# polarshield3_0c-opl.net
KiCad netlist of a schematic drawn in EAGLE
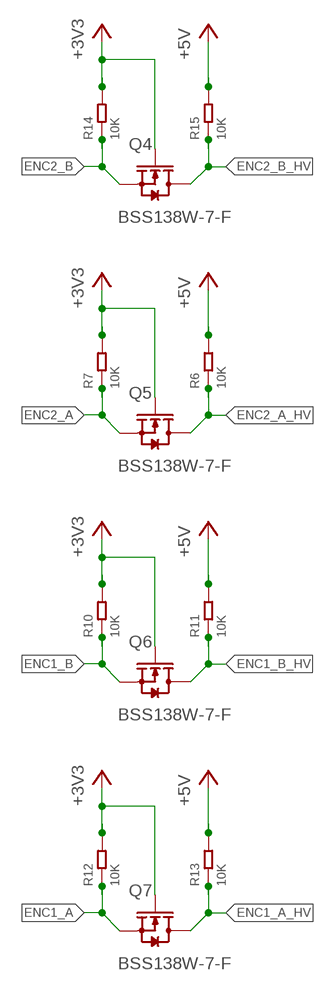
[diagram p0: schematic, sheet 1, part 1 of 2]
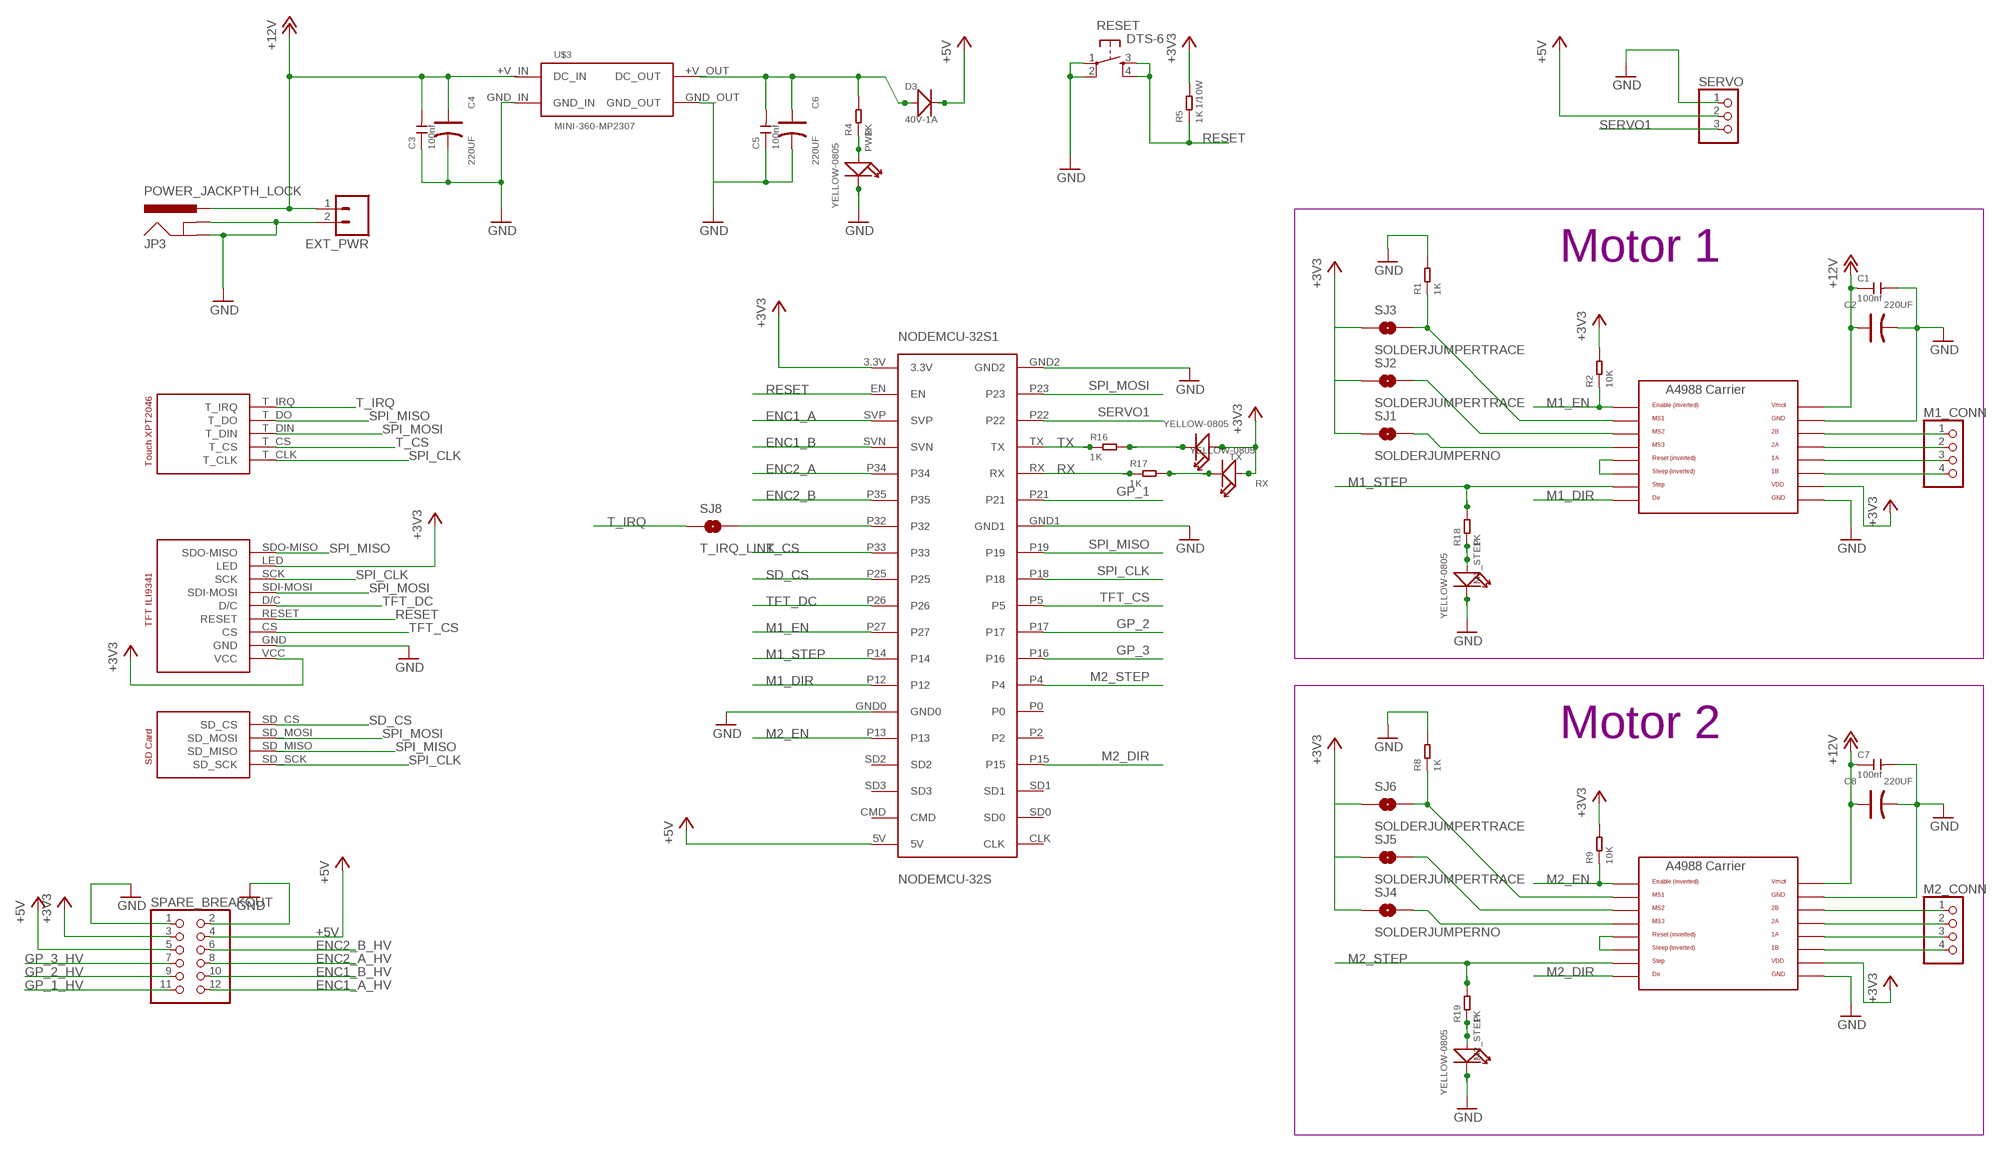
[diagram p1: schematic, sheet 1, part 2 of 2]

(export (version "E")
  (design (tool "Eeschema 10.0.6"))
  (components
    (comp (ref "C1")
      (value "100nf")
      (footprint "eagle-import:C0603")
      (fields (field (name "MPN") "CC0603KRX7R9BB104"))
      (libsource (lib "eagle-import") (part "CERAMIC-100NF-50V-10%-X7R(0603)"))
    )
    (comp (ref "C2")
      (value "220UF")
      (footprint "eagle-import:ELECTRO-SMD-C-6MM")
      (fields (field (name "MPN") "CS1E221M-CRE77"))
      (libsource (lib "eagle-import") (part "ALUMINUM-SMD-220UF-16V(D6.3-H7.7MM)"))
    )
    (comp (ref "C3")
      (value "100nf")
      (footprint "eagle-import:C0603")
      (fields (field (name "MPN") "CC0603KRX7R9BB104"))
      (libsource (lib "eagle-import") (part "CERAMIC-100NF-50V-10%-X7R(0603)"))
    )
    (comp (ref "C4")
      (value "220UF")
      (footprint "eagle-import:ELECTRO-SMD-C-6MM")
      (fields (field (name "MPN") "CS1E221M-CRE77"))
      (libsource (lib "eagle-import") (part "ALUMINUM-SMD-220UF-16V(D6.3-H7.7MM)"))
    )
    (comp (ref "C5")
      (value "100nf")
      (footprint "eagle-import:C0603")
      (fields (field (name "MPN") "CC0603KRX7R9BB104"))
      (libsource (lib "eagle-import") (part "CERAMIC-100NF-50V-10%-X7R(0603)"))
    )
    (comp (ref "C6")
      (value "220UF")
      (footprint "eagle-import:ELECTRO-SMD-C-6MM")
      (fields (field (name "MPN") "CS1E221M-CRE77"))
      (libsource (lib "eagle-import") (part "ALUMINUM-SMD-220UF-16V(D6.3-H7.7MM)"))
    )
    (comp (ref "C7")
      (value "100nf")
      (footprint "eagle-import:C0603")
      (fields (field (name "MPN") "CC0603KRX7R9BB104"))
      (libsource (lib "eagle-import") (part "CERAMIC-100NF-50V-10%-X7R(0603)"))
    )
    (comp (ref "C8")
      (value "220UF")
      (footprint "eagle-import:ELECTRO-SMD-C-6MM")
      (fields (field (name "MPN") "CS1E221M-CRE77"))
      (libsource (lib "eagle-import") (part "ALUMINUM-SMD-220UF-16V(D6.3-H7.7MM)"))
    )
    (comp (ref "D3")
      (value "40V-1A")
      (footprint "eagle-import:DO-214AC")
      (fields (field (name "MPN") "1N5819"))
      (libsource (lib "eagle-import") (part "SMD-DIODE-SCHOTTKY-40V-1A(DO-214AC)"))
    )
    (comp (ref "EXT_PWR")
      (value "M02PTH")
      (footprint "eagle-import:1X02")
      (libsource (lib "eagle-import") (part "M02PTH"))
    )
    (comp (ref "JP3")
      (value "POWER_JACKPTH_LOCK")
      (footprint "eagle-import:POWER_JACK_PTH_LOCK")
      (libsource (lib "eagle-import") (part "POWER_JACKPTH_LOCK"))
    )
    (comp (ref "M1_CONN")
      (value "PINHD-1X4/90")
      (footprint "eagle-import:1X04_90")
      (libsource (lib "eagle-import") (part "PINHD-1X4/90"))
    )
    (comp (ref "M1_STEP")
      (value "YELLOW-0805")
      (footprint "eagle-import:LED-0805")
      (fields (field (name "MPN") "17-215UYC/S530-A3/TR8"))
      (libsource (lib "eagle-import") (part "SMD-LED-CLEAR-YELLOW(0805)"))
    )
    (comp (ref "M2_CONN")
      (value "PINHD-1X4/90")
      (footprint "eagle-import:1X04_90")
      (libsource (lib "eagle-import") (part "PINHD-1X4/90"))
    )
    (comp (ref "M2_STEP")
      (value "YELLOW-0805")
      (footprint "eagle-import:LED-0805")
      (fields (field (name "MPN") "17-215UYC/S530-A3/TR8"))
      (libsource (lib "eagle-import") (part "SMD-LED-CLEAR-YELLOW(0805)"))
    )
    (comp (ref "MOTOR_1")
      (value "A4988BREAKOUT")
      (footprint "eagle-import:A4988BREAKOUT")
      (libsource (lib "eagle-import") (part "A4988BREAKOUT"))
    )
    (comp (ref "MOTOR_2")
      (value "A4988BREAKOUT")
      (footprint "eagle-import:A4988BREAKOUT")
      (libsource (lib "eagle-import") (part "A4988BREAKOUT"))
    )
    (comp (ref "NODEMCU-32S1")
      (value "NODEMCU-32S")
      (footprint "eagle-import:NODEMCU-32S")
      (libsource (lib "eagle-import") (part "NODEMCU-32S"))
    )
    (comp (ref "PWR")
      (value "YELLOW-0805")
      (footprint "eagle-import:LED-0805")
      (fields (field (name "MPN") "17-215UYC/S530-A3/TR8"))
      (libsource (lib "eagle-import") (part "SMD-LED-CLEAR-YELLOW(0805)"))
    )
    (comp (ref "Q4")
      (value "BSS138W-7-F")
      (footprint "eagle-import:SOT-23")
      (libsource (lib "eagle-import") (part "SMD-MOSFET-N-CH-50V-200MA-BSS138W-7-F(SOT-23)"))
    )
    (comp (ref "Q5")
      (value "BSS138W-7-F")
      (footprint "eagle-import:SOT-23")
      (libsource (lib "eagle-import") (part "SMD-MOSFET-N-CH-50V-200MA-BSS138W-7-F(SOT-23)"))
    )
    (comp (ref "Q6")
      (value "BSS138W-7-F")
      (footprint "eagle-import:SOT-23")
      (libsource (lib "eagle-import") (part "SMD-MOSFET-N-CH-50V-200MA-BSS138W-7-F(SOT-23)"))
    )
    (comp (ref "Q7")
      (value "BSS138W-7-F")
      (footprint "eagle-import:SOT-23")
      (libsource (lib "eagle-import") (part "SMD-MOSFET-N-CH-50V-200MA-BSS138W-7-F(SOT-23)"))
    )
    (comp (ref "R1")
      (value "1K")
      (footprint "eagle-import:R0603")
      (fields (field (name "MPN") "RC0603JR-071KL"))
      (libsource (lib "eagle-import") (part "SMD-RES-1K-5%-1/10W(0603)"))
    )
    (comp (ref "R2")
      (value "10K")
      (footprint "eagle-import:R0603")
      (fields (field (name "MPN") "RC0603JR-0710KL"))
      (libsource (lib "eagle-import") (part "SMD-RES-10K-5%-1/10W(0603)"))
    )
    (comp (ref "R4")
      (value "1K")
      (footprint "eagle-import:R0603")
      (fields (field (name "MPN") "RC0603JR-071KL"))
      (libsource (lib "eagle-import") (part "SMD-RES-1K-5%-1/10W(0603)"))
    )
    (comp (ref "R5")
      (value "1K 1/10W")
      (footprint "eagle-import:R0603")
      (fields (field (name "MPN") "RC0603JR-071KL"))
      (libsource (lib "eagle-import") (part "SMD-RES-1K-5%-1/10W(0603)"))
    )
    (comp (ref "R6")
      (value "10K")
      (footprint "eagle-import:R0603")
      (fields (field (name "MPN") "RC0603JR-0710KL"))
      (libsource (lib "eagle-import") (part "SMD-RES-10K-5%-1/10W(0603)"))
    )
    (comp (ref "R7")
      (value "10K")
      (footprint "eagle-import:R0603")
      (fields (field (name "MPN") "RC0603JR-0710KL"))
      (libsource (lib "eagle-import") (part "SMD-RES-10K-5%-1/10W(0603)"))
    )
    (comp (ref "R8")
      (value "1K")
      (footprint "eagle-import:R0603")
      (fields (field (name "MPN") "RC0603JR-071KL"))
      (libsource (lib "eagle-import") (part "SMD-RES-1K-5%-1/10W(0603)"))
    )
    (comp (ref "R9")
      (value "10K")
      (footprint "eagle-import:R0603")
      (fields (field (name "MPN") "RC0603JR-0710KL"))
      (libsource (lib "eagle-import") (part "SMD-RES-10K-5%-1/10W(0603)"))
    )
    (comp (ref "R10")
      (value "10K")
      (footprint "eagle-import:R0603")
      (fields (field (name "MPN") "RC0603JR-0710KL"))
      (libsource (lib "eagle-import") (part "SMD-RES-10K-5%-1/10W(0603)"))
    )
    (comp (ref "R11")
      (value "10K")
      (footprint "eagle-import:R0603")
      (fields (field (name "MPN") "RC0603JR-0710KL"))
      (libsource (lib "eagle-import") (part "SMD-RES-10K-5%-1/10W(0603)"))
    )
    (comp (ref "R12")
      (value "10K")
      (footprint "eagle-import:R0603")
      (fields (field (name "MPN") "RC0603JR-0710KL"))
      (libsource (lib "eagle-import") (part "SMD-RES-10K-5%-1/10W(0603)"))
    )
    (comp (ref "R13")
      (value "10K")
      (footprint "eagle-import:R0603")
      (fields (field (name "MPN") "RC0603JR-0710KL"))
      (libsource (lib "eagle-import") (part "SMD-RES-10K-5%-1/10W(0603)"))
    )
    (comp (ref "R14")
      (value "10K")
      (footprint "eagle-import:R0603")
      (fields (field (name "MPN") "RC0603JR-0710KL"))
      (libsource (lib "eagle-import") (part "SMD-RES-10K-5%-1/10W(0603)"))
    )
    (comp (ref "R15")
      (value "10K")
      (footprint "eagle-import:R0603")
      (fields (field (name "MPN") "RC0603JR-0710KL"))
      (libsource (lib "eagle-import") (part "SMD-RES-10K-5%-1/10W(0603)"))
    )
    (comp (ref "R16")
      (value "1K")
      (footprint "eagle-import:R0603")
      (fields (field (name "MPN") "RC0603JR-071KL"))
      (libsource (lib "eagle-import") (part "SMD-RES-1K-5%-1/10W(0603)"))
    )
    (comp (ref "R17")
      (value "1K")
      (footprint "eagle-import:R0603")
      (fields (field (name "MPN") "RC0603JR-071KL"))
      (libsource (lib "eagle-import") (part "SMD-RES-1K-5%-1/10W(0603)"))
    )
    (comp (ref "R18")
      (value "1K")
      (footprint "eagle-import:R0603")
      (fields (field (name "MPN") "RC0603JR-071KL"))
      (libsource (lib "eagle-import") (part "SMD-RES-1K-5%-1/10W(0603)"))
    )
    (comp (ref "R19")
      (value "1K")
      (footprint "eagle-import:R0603")
      (fields (field (name "MPN") "RC0603JR-071KL"))
      (libsource (lib "eagle-import") (part "SMD-RES-1K-5%-1/10W(0603)"))
    )
    (comp (ref "RESET")
      (value "DTS-6")
      (footprint "eagle-import:DTS-6")
      (libsource (lib "eagle-import") (part "DTS-6"))
    )
    (comp (ref "RX")
      (value "YELLOW-0805")
      (footprint "eagle-import:LED-0805")
      (fields (field (name "MPN") "17-215UYC/S530-A3/TR8"))
      (libsource (lib "eagle-import") (part "SMD-LED-CLEAR-YELLOW(0805)"))
    )
    (comp (ref "SERVO")
      (value "PINHD-1X3/90")
      (footprint "eagle-import:1X03_90")
      (libsource (lib "eagle-import") (part "PINHD-1X3/90"))
    )
    (comp (ref "SJ1")
      (value "SOLDERJUMPERNO")
      (footprint "eagle-import:SJ_2S-NO")
      (libsource (lib "eagle-import") (part "polargraph3_SOLDERJUMPERNO"))
    )
    (comp (ref "SJ2")
      (value "SOLDERJUMPERTRACE")
      (footprint "eagle-import:SJ_2S-TRACE")
      (libsource (lib "eagle-import") (part "polargraph3_SOLDERJUMPERTRACE"))
    )
    (comp (ref "SJ3")
      (value "SOLDERJUMPERTRACE")
      (footprint "eagle-import:SJ_2S-TRACE")
      (libsource (lib "eagle-import") (part "polargraph3_SOLDERJUMPERTRACE"))
    )
    (comp (ref "SJ4")
      (value "SOLDERJUMPERNO")
      (footprint "eagle-import:SJ_2S-NO")
      (libsource (lib "eagle-import") (part "polargraph3_SOLDERJUMPERNO"))
    )
    (comp (ref "SJ5")
      (value "SOLDERJUMPERTRACE")
      (footprint "eagle-import:SJ_2S-TRACE")
      (libsource (lib "eagle-import") (part "polargraph3_SOLDERJUMPERTRACE"))
    )
    (comp (ref "SJ6")
      (value "SOLDERJUMPERTRACE")
      (footprint "eagle-import:SJ_2S-TRACE")
      (libsource (lib "eagle-import") (part "polargraph3_SOLDERJUMPERTRACE"))
    )
    (comp (ref "SJ8")
      (value "T_IRQ_LINK")
      (footprint "eagle-import:SJ_2S-NO")
      (libsource (lib "eagle-import") (part "SOLDERJUMPERNO"))
    )
    (comp (ref "SPARE_BREAKOUT")
      (value "PINHD-2X6")
      (footprint "eagle-import:2X06")
      (libsource (lib "eagle-import") (part "PINHD-2X6"))
    )
    (comp (ref "TX")
      (value "YELLOW-0805")
      (footprint "eagle-import:LED-0805")
      (fields (field (name "MPN") "17-215UYC/S530-A3/TR8"))
      (libsource (lib "eagle-import") (part "SMD-LED-CLEAR-YELLOW(0805)"))
    )
    (comp (ref "U$2")
      (value "2.4_TFT_SPI_TOUCH_SD")
      (footprint "eagle-import:2.4_TFT_SPI_TOUCH_SD")
      (libsource (lib "eagle-import") (part "2.4_TFT_SPI_TOUCH_SD"))
    )
    (comp (ref "U$3")
      (value "MINI-360-MP2307")
      (footprint "eagle-import:MINI-360-MP2307")
      (libsource (lib "eagle-import") (part "MINI-360-MP2307"))
    )
  )
  (nets
    (net (code "1") (name "+3V3") (class "Default")
      (node (ref "MOTOR_1") (pin "VDD") (pinfunction "VDD_VDD") (pintype "power_in"))
      (node (ref "MOTOR_2") (pin "VDD") (pinfunction "VDD_VDD") (pintype "power_in"))
      (node (ref "NODEMCU-32S1") (pin "3.3V") (pinfunction "3.3V_3.3V") (pintype "bidirectional"))
      (node (ref "Q4") (pin "1") (pinfunction "G_1") (pintype "passive"))
      (node (ref "Q5") (pin "1") (pinfunction "G_1") (pintype "passive"))
      (node (ref "Q6") (pin "1") (pinfunction "G_1") (pintype "passive"))
      (node (ref "Q7") (pin "1") (pinfunction "G_1") (pintype "passive"))
      (node (ref "R10") (pin "2") (pinfunction "2_2") (pintype "passive"))
      (node (ref "R12") (pin "2") (pinfunction "2_2") (pintype "passive"))
      (node (ref "R14") (pin "2") (pinfunction "2_2") (pintype "passive"))
      (node (ref "R2") (pin "2") (pinfunction "2_2") (pintype "passive"))
      (node (ref "R5") (pin "2") (pinfunction "2_2") (pintype "passive"))
      (node (ref "R7") (pin "2") (pinfunction "2_2") (pintype "passive"))
      (node (ref "R9") (pin "2") (pinfunction "2_2") (pintype "passive"))
      (node (ref "RX") (pin "+") (pinfunction "+_+") (pintype "passive"))
      (node (ref "SJ1") (pin "1") (pinfunction "1_1") (pintype "passive"))
      (node (ref "SJ2") (pin "1") (pinfunction "1_1") (pintype "passive"))
      (node (ref "SJ3") (pin "1") (pinfunction "1_1") (pintype "passive"))
      (node (ref "SJ4") (pin "1") (pinfunction "1_1") (pintype "passive"))
      (node (ref "SJ5") (pin "1") (pinfunction "1_1") (pintype "passive"))
      (node (ref "SJ6") (pin "1") (pinfunction "1_1") (pintype "passive"))
      (node (ref "SPARE_BREAKOUT") (pin "3") (pinfunction "3_3") (pintype "passive"))
      (node (ref "TX") (pin "+") (pinfunction "+_+") (pintype "passive"))
      (node (ref "U$2") (pin "LED") (pinfunction "LED_LED") (pintype "bidirectional"))
      (node (ref "U$2") (pin "VCC") (pinfunction "VCC_VCC") (pintype "bidirectional"))
    )
    (net (code "2") (name "+5V") (class "Default")
      (node (ref "D3") (pin "2") (pinfunction "-_2") (pintype "passive"))
      (node (ref "NODEMCU-32S1") (pin "5V") (pinfunction "5V_5V") (pintype "bidirectional"))
      (node (ref "R11") (pin "2") (pinfunction "2_2") (pintype "passive"))
      (node (ref "R13") (pin "2") (pinfunction "2_2") (pintype "passive"))
      (node (ref "R15") (pin "2") (pinfunction "2_2") (pintype "passive"))
      (node (ref "R6") (pin "2") (pinfunction "2_2") (pintype "passive"))
      (node (ref "SERVO") (pin "2") (pinfunction "2_2") (pintype "passive"))
      (node (ref "SPARE_BREAKOUT") (pin "4") (pinfunction "4_4") (pintype "passive"))
      (node (ref "SPARE_BREAKOUT") (pin "5") (pinfunction "5_5") (pintype "passive"))
    )
    (net (code "3") (name "+12V") (class "Default")
      (node (ref "C1") (pin "1") (pinfunction "1_1") (pintype "passive"))
      (node (ref "C2") (pin "+") (pinfunction "+_+") (pintype "passive"))
      (node (ref "C3") (pin "2") (pinfunction "2_2") (pintype "passive"))
      (node (ref "C4") (pin "+") (pinfunction "+_+") (pintype "passive"))
      (node (ref "C7") (pin "1") (pinfunction "1_1") (pintype "passive"))
      (node (ref "C8") (pin "+") (pinfunction "+_+") (pintype "passive"))
      (node (ref "EXT_PWR") (pin "1") (pinfunction "1_1") (pintype "passive"))
      (node (ref "JP3") (pin "PWR") (pinfunction "PWR_PWR") (pintype "bidirectional"))
      (node (ref "MOTOR_1") (pin "VMOT") (pinfunction "VMOT_VMOT") (pintype "power_in"))
      (node (ref "MOTOR_2") (pin "VMOT") (pinfunction "VMOT_VMOT") (pintype "power_in"))
      (node (ref "U$3") (pin "+V_IN") (pinfunction "DC_IN_+V_IN") (pintype "bidirectional"))
    )
    (net (code "4") (name "/GP_1") (class "Default")
      (node (ref "NODEMCU-32S1") (pin "P21") (pinfunction "P21_P21") (pintype "bidirectional"))
    )
    (net (code "5") (name "/GP_1_HV") (class "Default")
      (node (ref "SPARE_BREAKOUT") (pin "11") (pinfunction "11_11") (pintype "passive"))
    )
    (net (code "6") (name "/GP_2") (class "Default")
      (node (ref "NODEMCU-32S1") (pin "P17") (pinfunction "P17_P17") (pintype "bidirectional"))
    )
    (net (code "7") (name "/GP_2_HV") (class "Default")
      (node (ref "SPARE_BREAKOUT") (pin "9") (pinfunction "9_9") (pintype "passive"))
    )
    (net (code "8") (name "/GP_3") (class "Default")
      (node (ref "NODEMCU-32S1") (pin "P16") (pinfunction "P16_P16") (pintype "bidirectional"))
    )
    (net (code "9") (name "/GP_3_HV") (class "Default")
      (node (ref "SPARE_BREAKOUT") (pin "7") (pinfunction "7_7") (pintype "passive"))
    )
    (net (code "10") (name "/M1_DIR") (class "Default")
      (node (ref "MOTOR_1") (pin "DIR") (pinfunction "DIR_DIR") (pintype "input"))
      (node (ref "NODEMCU-32S1") (pin "P12") (pinfunction "P12_P12") (pintype "bidirectional"))
    )
    (net (code "11") (name "/M1_EN") (class "Default")
      (node (ref "MOTOR_1") (pin "EN") (pinfunction "EN_EN") (pintype "input"))
      (node (ref "NODEMCU-32S1") (pin "P27") (pinfunction "P27_P27") (pintype "bidirectional"))
      (node (ref "R2") (pin "1") (pinfunction "1_1") (pintype "passive"))
    )
    (net (code "12") (name "/M1_STEP") (class "Default")
      (node (ref "MOTOR_1") (pin "STEP") (pinfunction "STEP_STEP") (pintype "input"))
      (node (ref "NODEMCU-32S1") (pin "P14") (pinfunction "P14_P14") (pintype "bidirectional"))
      (node (ref "R18") (pin "2") (pinfunction "2_2") (pintype "passive"))
    )
    (net (code "13") (name "/M2_DIR") (class "Default")
      (node (ref "MOTOR_2") (pin "DIR") (pinfunction "DIR_DIR") (pintype "input"))
      (node (ref "NODEMCU-32S1") (pin "P15") (pinfunction "P15_P15") (pintype "bidirectional"))
    )
    (net (code "14") (name "/M2_EN") (class "Default")
      (node (ref "MOTOR_2") (pin "EN") (pinfunction "EN_EN") (pintype "input"))
      (node (ref "NODEMCU-32S1") (pin "P13") (pinfunction "P13_P13") (pintype "bidirectional"))
      (node (ref "R9") (pin "1") (pinfunction "1_1") (pintype "passive"))
    )
    (net (code "15") (name "/M2_STEP") (class "Default")
      (node (ref "MOTOR_2") (pin "STEP") (pinfunction "STEP_STEP") (pintype "input"))
      (node (ref "NODEMCU-32S1") (pin "P4") (pinfunction "P4_P4") (pintype "bidirectional"))
      (node (ref "R19") (pin "2") (pinfunction "2_2") (pintype "passive"))
    )
    (net (code "16") (name "/RESET") (class "Default")
      (node (ref "NODEMCU-32S1") (pin "EN") (pinfunction "EN_EN") (pintype "bidirectional"))
      (node (ref "R5") (pin "1") (pinfunction "1_1") (pintype "passive"))
      (node (ref "RESET") (pin "3") (pinfunction "3_3") (pintype "passive"))
      (node (ref "RESET") (pin "4") (pinfunction "4_4") (pintype "passive"))
      (node (ref "U$2") (pin "RESET") (pinfunction "RESET_RESET") (pintype "bidirectional"))
    )
    (net (code "17") (name "/RX") (class "Default")
      (node (ref "NODEMCU-32S1") (pin "RX") (pinfunction "RX_RX") (pintype "bidirectional"))
      (node (ref "R17") (pin "1") (pinfunction "1_1") (pintype "passive"))
    )
    (net (code "18") (name "/SD_CS") (class "Default")
      (node (ref "NODEMCU-32S1") (pin "P25") (pinfunction "P25_P25") (pintype "bidirectional"))
      (node (ref "U$2") (pin "SD_CS") (pinfunction "SD_CS_SD_CS") (pintype "bidirectional"))
    )
    (net (code "19") (name "/SERVO1") (class "Default")
      (node (ref "NODEMCU-32S1") (pin "P22") (pinfunction "P22_P22") (pintype "bidirectional"))
      (node (ref "SERVO") (pin "3") (pinfunction "3_3") (pintype "passive"))
    )
    (net (code "20") (name "/SPI_CLK") (class "Default")
      (node (ref "NODEMCU-32S1") (pin "P18") (pinfunction "P18_P18") (pintype "bidirectional"))
      (node (ref "U$2") (pin "SCK") (pinfunction "SCK_SCK") (pintype "bidirectional"))
      (node (ref "U$2") (pin "SD_SCK") (pinfunction "SD_SCK_SD_SCK") (pintype "bidirectional"))
      (node (ref "U$2") (pin "T_CLK") (pinfunction "T_CLK_T_CLK") (pintype "input"))
    )
    (net (code "21") (name "/SPI_MISO") (class "Default")
      (node (ref "NODEMCU-32S1") (pin "P19") (pinfunction "P19_P19") (pintype "bidirectional"))
      (node (ref "U$2") (pin "SDO-MISO") (pinfunction "SDO-MISO_SDO-MISO") (pintype "bidirectional"))
      (node (ref "U$2") (pin "SD_MISO") (pinfunction "SD_MISO_SD_MISO") (pintype "bidirectional"))
      (node (ref "U$2") (pin "T_DO") (pinfunction "T_DO_T_DO") (pintype "output"))
    )
    (net (code "22") (name "/SPI_MOSI") (class "Default")
      (node (ref "NODEMCU-32S1") (pin "P23") (pinfunction "P23_P23") (pintype "bidirectional"))
      (node (ref "U$2") (pin "SDI-MOSI") (pinfunction "SDI-MOSI_SDI-MOSI") (pintype "bidirectional"))
      (node (ref "U$2") (pin "SD_MOSI") (pinfunction "SD_MOSI_SD_MOSI") (pintype "bidirectional"))
      (node (ref "U$2") (pin "T_DIN") (pinfunction "T_DIN_T_DIN") (pintype "input"))
    )
    (net (code "23") (name "/TFT_CS") (class "Default")
      (node (ref "NODEMCU-32S1") (pin "P5") (pinfunction "P5_P5") (pintype "bidirectional"))
      (node (ref "U$2") (pin "CS") (pinfunction "CS_CS") (pintype "bidirectional"))
    )
    (net (code "24") (name "/TFT_DC") (class "Default")
      (node (ref "NODEMCU-32S1") (pin "P26") (pinfunction "P26_P26") (pintype "bidirectional"))
      (node (ref "U$2") (pin "D/C") (pinfunction "D/C_D/C") (pintype "bidirectional"))
    )
    (net (code "25") (name "/TX") (class "Default")
      (node (ref "NODEMCU-32S1") (pin "TX") (pinfunction "TX_TX") (pintype "bidirectional"))
      (node (ref "R16") (pin "1") (pinfunction "1_1") (pintype "passive"))
    )
    (net (code "26") (name "/T_CS") (class "Default")
      (node (ref "NODEMCU-32S1") (pin "P33") (pinfunction "P33_P33") (pintype "bidirectional"))
      (node (ref "U$2") (pin "T_CS") (pinfunction "T_CS_T_CS") (pintype "output"))
    )
    (net (code "27") (name "/T_IRQ") (class "Default")
      (node (ref "SJ8") (pin "1") (pinfunction "1_1") (pintype "passive"))
      (node (ref "U$2") (pin "T_IRQ") (pinfunction "T_IRQ_T_IRQ") (pintype "output"))
    )
    (net (code "28") (name "ENC1_A") (class "Default")
      (node (ref "NODEMCU-32S1") (pin "SVP") (pinfunction "SVP_SVP") (pintype "bidirectional"))
      (node (ref "Q7") (pin "2") (pinfunction "S_2") (pintype "passive"))
      (node (ref "R12") (pin "1") (pinfunction "1_1") (pintype "passive"))
    )
    (net (code "29") (name "ENC1_A_HV") (class "Default")
      (node (ref "Q7") (pin "3") (pinfunction "D_3") (pintype "passive"))
      (node (ref "R13") (pin "1") (pinfunction "1_1") (pintype "passive"))
      (node (ref "SPARE_BREAKOUT") (pin "12") (pinfunction "12_12") (pintype "passive"))
    )
    (net (code "30") (name "ENC1_B") (class "Default")
      (node (ref "NODEMCU-32S1") (pin "SVN") (pinfunction "SVN_SVN") (pintype "bidirectional"))
      (node (ref "Q6") (pin "2") (pinfunction "S_2") (pintype "passive"))
      (node (ref "R10") (pin "1") (pinfunction "1_1") (pintype "passive"))
    )
    (net (code "31") (name "ENC1_B_HV") (class "Default")
      (node (ref "Q6") (pin "3") (pinfunction "D_3") (pintype "passive"))
      (node (ref "R11") (pin "1") (pinfunction "1_1") (pintype "passive"))
      (node (ref "SPARE_BREAKOUT") (pin "10") (pinfunction "10_10") (pintype "passive"))
    )
    (net (code "32") (name "ENC2_A") (class "Default")
      (node (ref "NODEMCU-32S1") (pin "P34") (pinfunction "P34_P34") (pintype "bidirectional"))
      (node (ref "Q5") (pin "2") (pinfunction "S_2") (pintype "passive"))
      (node (ref "R7") (pin "1") (pinfunction "1_1") (pintype "passive"))
    )
    (net (code "33") (name "ENC2_A_HV") (class "Default")
      (node (ref "Q5") (pin "3") (pinfunction "D_3") (pintype "passive"))
      (node (ref "R6") (pin "1") (pinfunction "1_1") (pintype "passive"))
      (node (ref "SPARE_BREAKOUT") (pin "8") (pinfunction "8_8") (pintype "passive"))
    )
    (net (code "34") (name "ENC2_B") (class "Default")
      (node (ref "NODEMCU-32S1") (pin "P35") (pinfunction "P35_P35") (pintype "bidirectional"))
      (node (ref "Q4") (pin "2") (pinfunction "S_2") (pintype "passive"))
      (node (ref "R14") (pin "1") (pinfunction "1_1") (pintype "passive"))
    )
    (net (code "35") (name "ENC2_B_HV") (class "Default")
      (node (ref "Q4") (pin "3") (pinfunction "D_3") (pintype "passive"))
      (node (ref "R15") (pin "1") (pinfunction "1_1") (pintype "passive"))
      (node (ref "SPARE_BREAKOUT") (pin "6") (pinfunction "6_6") (pintype "passive"))
    )
    (net (code "36") (name "GND") (class "Default")
      (node (ref "C1") (pin "2") (pinfunction "2_2") (pintype "passive"))
      (node (ref "C2") (pin "-") (pinfunction "-_-") (pintype "passive"))
      (node (ref "C3") (pin "1") (pinfunction "1_1") (pintype "passive"))
      (node (ref "C4") (pin "-") (pinfunction "-_-") (pintype "passive"))
      (node (ref "C5") (pin "1") (pinfunction "1_1") (pintype "passive"))
      (node (ref "C6") (pin "-") (pinfunction "-_-") (pintype "passive"))
      (node (ref "C7") (pin "2") (pinfunction "2_2") (pintype "passive"))
      (node (ref "C8") (pin "-") (pinfunction "-_-") (pintype "passive"))
      (node (ref "EXT_PWR") (pin "2") (pinfunction "2_2") (pintype "passive"))
      (node (ref "JP3") (pin "GND") (pinfunction "GND_GND") (pintype "bidirectional"))
      (node (ref "JP3") (pin "GNDBREAK") (pinfunction "GNDBREAK_GNDBREAK") (pintype "bidirectional"))
      (node (ref "M1_STEP") (pin "-") (pinfunction "-_-") (pintype "passive"))
      (node (ref "M2_STEP") (pin "-") (pinfunction "-_-") (pintype "passive"))
      (node (ref "MOTOR_1") (pin "GND") (pinfunction "GND_GND") (pintype "power_in"))
      (node (ref "MOTOR_1") (pin "GND@0") (pinfunction "GND_GND@0") (pintype "power_in"))
      (node (ref "MOTOR_2") (pin "GND") (pinfunction "GND_GND") (pintype "power_in"))
      (node (ref "MOTOR_2") (pin "GND@0") (pinfunction "GND_GND@0") (pintype "power_in"))
      (node (ref "NODEMCU-32S1") (pin "GND0") (pinfunction "GND0_GND0") (pintype "bidirectional"))
      (node (ref "NODEMCU-32S1") (pin "GND1") (pinfunction "GND1_GND1") (pintype "bidirectional"))
      (node (ref "NODEMCU-32S1") (pin "GND2") (pinfunction "GND2_GND2") (pintype "bidirectional"))
      (node (ref "PWR") (pin "-") (pinfunction "-_-") (pintype "passive"))
      (node (ref "R1") (pin "2") (pinfunction "2_2") (pintype "passive"))
      (node (ref "R8") (pin "2") (pinfunction "2_2") (pintype "passive"))
      (node (ref "RESET") (pin "1") (pinfunction "1_1") (pintype "passive"))
      (node (ref "RESET") (pin "2") (pinfunction "2_2") (pintype "passive"))
      (node (ref "SERVO") (pin "1") (pinfunction "1_1") (pintype "passive"))
      (node (ref "SPARE_BREAKOUT") (pin "1") (pinfunction "1_1") (pintype "passive"))
      (node (ref "SPARE_BREAKOUT") (pin "2") (pinfunction "2_2") (pintype "passive"))
      (node (ref "U$2") (pin "GND") (pinfunction "GND_GND") (pintype "bidirectional"))
      (node (ref "U$3") (pin "GND_IN") (pinfunction "GND_IN_GND_IN") (pintype "bidirectional"))
      (node (ref "U$3") (pin "GND_OUT") (pinfunction "GND_OUT_GND_OUT") (pintype "bidirectional"))
    )
    (net (code "37") (name "Net-(D3-+)") (class "Default")
      (node (ref "C5") (pin "2") (pinfunction "2_2") (pintype "passive"))
      (node (ref "C6") (pin "+") (pinfunction "+_+") (pintype "passive"))
      (node (ref "D3") (pin "1") (pinfunction "+_1") (pintype "passive"))
      (node (ref "R4") (pin "2") (pinfunction "2_2") (pintype "passive"))
      (node (ref "U$3") (pin "+V_OUT") (pinfunction "DC_OUT_+V_OUT") (pintype "bidirectional"))
    )
    (net (code "38") (name "Net-(M1_CONN-Pad1)") (class "Default")
      (node (ref "M1_CONN") (pin "1") (pinfunction "1_1") (pintype "passive"))
      (node (ref "MOTOR_1") (pin "2B") (pinfunction "2B_2B") (pintype "output"))
    )
    (net (code "39") (name "Net-(M1_CONN-Pad2)") (class "Default")
      (node (ref "M1_CONN") (pin "2") (pinfunction "2_2") (pintype "passive"))
      (node (ref "MOTOR_1") (pin "2A") (pinfunction "2A_2A") (pintype "output"))
    )
    (net (code "40") (name "Net-(M1_CONN-Pad3)") (class "Default")
      (node (ref "M1_CONN") (pin "3") (pinfunction "3_3") (pintype "passive"))
      (node (ref "MOTOR_1") (pin "1A") (pinfunction "1A_1A") (pintype "output"))
    )
    (net (code "41") (name "Net-(M1_CONN-Pad4)") (class "Default")
      (node (ref "M1_CONN") (pin "4") (pinfunction "4_4") (pintype "passive"))
      (node (ref "MOTOR_1") (pin "1B") (pinfunction "1B_1B") (pintype "output"))
    )
    (net (code "42") (name "Net-(M1_STEP-Pad+)") (class "Default")
      (node (ref "M1_STEP") (pin "+") (pinfunction "+_+") (pintype "passive"))
      (node (ref "R18") (pin "1") (pinfunction "1_1") (pintype "passive"))
    )
    (net (code "43") (name "Net-(M2_CONN-Pad1)") (class "Default")
      (node (ref "M2_CONN") (pin "1") (pinfunction "1_1") (pintype "passive"))
      (node (ref "MOTOR_2") (pin "2B") (pinfunction "2B_2B") (pintype "output"))
    )
    (net (code "44") (name "Net-(M2_CONN-Pad2)") (class "Default")
      (node (ref "M2_CONN") (pin "2") (pinfunction "2_2") (pintype "passive"))
      (node (ref "MOTOR_2") (pin "2A") (pinfunction "2A_2A") (pintype "output"))
    )
    (net (code "45") (name "Net-(M2_CONN-Pad3)") (class "Default")
      (node (ref "M2_CONN") (pin "3") (pinfunction "3_3") (pintype "passive"))
      (node (ref "MOTOR_2") (pin "1A") (pinfunction "1A_1A") (pintype "output"))
    )
    (net (code "46") (name "Net-(M2_CONN-Pad4)") (class "Default")
      (node (ref "M2_CONN") (pin "4") (pinfunction "4_4") (pintype "passive"))
      (node (ref "MOTOR_2") (pin "1B") (pinfunction "1B_1B") (pintype "output"))
    )
    (net (code "47") (name "Net-(M2_STEP-Pad+)") (class "Default")
      (node (ref "M2_STEP") (pin "+") (pinfunction "+_+") (pintype "passive"))
      (node (ref "R19") (pin "1") (pinfunction "1_1") (pintype "passive"))
    )
    (net (code "48") (name "Net-(MOTOR_1-PadMS1)") (class "Default")
      (node (ref "MOTOR_1") (pin "MS1") (pinfunction "MS1_MS1") (pintype "input"))
      (node (ref "R1") (pin "1") (pinfunction "1_1") (pintype "passive"))
      (node (ref "SJ3") (pin "2") (pinfunction "2_2") (pintype "passive"))
    )
    (net (code "49") (name "Net-(MOTOR_1-PadMS2)") (class "Default")
      (node (ref "MOTOR_1") (pin "MS2") (pinfunction "MS2_MS2") (pintype "input"))
      (node (ref "SJ2") (pin "2") (pinfunction "2_2") (pintype "passive"))
    )
    (net (code "50") (name "Net-(MOTOR_1-PadMS3)") (class "Default")
      (node (ref "MOTOR_1") (pin "MS3") (pinfunction "MS3_MS3") (pintype "input"))
      (node (ref "SJ1") (pin "2") (pinfunction "2_2") (pintype "passive"))
    )
    (net (code "51") (name "Net-(MOTOR_1-SLEEP)") (class "Default")
      (node (ref "MOTOR_1") (pin "RST") (pinfunction "RST_RST") (pintype "input"))
      (node (ref "MOTOR_1") (pin "SLP") (pinfunction "SLEEP_SLP") (pintype "input"))
    )
    (net (code "52") (name "Net-(MOTOR_2-PadMS1)") (class "Default")
      (node (ref "MOTOR_2") (pin "MS1") (pinfunction "MS1_MS1") (pintype "input"))
      (node (ref "R8") (pin "1") (pinfunction "1_1") (pintype "passive"))
      (node (ref "SJ6") (pin "2") (pinfunction "2_2") (pintype "passive"))
    )
    (net (code "53") (name "Net-(MOTOR_2-PadMS2)") (class "Default")
      (node (ref "MOTOR_2") (pin "MS2") (pinfunction "MS2_MS2") (pintype "input"))
      (node (ref "SJ5") (pin "2") (pinfunction "2_2") (pintype "passive"))
    )
    (net (code "54") (name "Net-(MOTOR_2-PadMS3)") (class "Default")
      (node (ref "MOTOR_2") (pin "MS3") (pinfunction "MS3_MS3") (pintype "input"))
      (node (ref "SJ4") (pin "2") (pinfunction "2_2") (pintype "passive"))
    )
    (net (code "55") (name "Net-(MOTOR_2-SLEEP)") (class "Default")
      (node (ref "MOTOR_2") (pin "RST") (pinfunction "RST_RST") (pintype "input"))
      (node (ref "MOTOR_2") (pin "SLP") (pinfunction "SLEEP_SLP") (pintype "input"))
    )
    (net (code "56") (name "Net-(NODEMCU-32S1-PadP32)") (class "Default")
      (node (ref "NODEMCU-32S1") (pin "P32") (pinfunction "P32_P32") (pintype "bidirectional"))
      (node (ref "SJ8") (pin "2") (pinfunction "2_2") (pintype "passive"))
    )
    (net (code "57") (name "Net-(PWR-Pad+)") (class "Default")
      (node (ref "PWR") (pin "+") (pinfunction "+_+") (pintype "passive"))
      (node (ref "R4") (pin "1") (pinfunction "1_1") (pintype "passive"))
    )
    (net (code "58") (name "Net-(R16-Pad2)") (class "Default")
      (node (ref "R16") (pin "2") (pinfunction "2_2") (pintype "passive"))
      (node (ref "TX") (pin "-") (pinfunction "-_-") (pintype "passive"))
    )
    (net (code "59") (name "Net-(R17-Pad2)") (class "Default")
      (node (ref "R17") (pin "2") (pinfunction "2_2") (pintype "passive"))
      (node (ref "RX") (pin "-") (pinfunction "-_-") (pintype "passive"))
    )
    (net (code "60") (name "unconnected-(NODEMCU-32S1-PadCLK)") (class "Default")
      (node (ref "NODEMCU-32S1") (pin "CLK") (pinfunction "CLK_CLK") (pintype "bidirectional"))
    )
    (net (code "61") (name "unconnected-(NODEMCU-32S1-PadCMD)") (class "Default")
      (node (ref "NODEMCU-32S1") (pin "CMD") (pinfunction "CMD_CMD") (pintype "bidirectional"))
    )
    (net (code "62") (name "unconnected-(NODEMCU-32S1-PadP0)") (class "Default")
      (node (ref "NODEMCU-32S1") (pin "P0") (pinfunction "P0_P0") (pintype "bidirectional"))
    )
    (net (code "63") (name "unconnected-(NODEMCU-32S1-PadP2)") (class "Default")
      (node (ref "NODEMCU-32S1") (pin "P2") (pinfunction "P2_P2") (pintype "bidirectional"))
    )
    (net (code "64") (name "unconnected-(NODEMCU-32S1-PadSD0)") (class "Default")
      (node (ref "NODEMCU-32S1") (pin "SD0") (pinfunction "SD0_SD0") (pintype "bidirectional"))
    )
    (net (code "65") (name "unconnected-(NODEMCU-32S1-PadSD1)") (class "Default")
      (node (ref "NODEMCU-32S1") (pin "SD1") (pinfunction "SD1_SD1") (pintype "bidirectional"))
    )
    (net (code "66") (name "unconnected-(NODEMCU-32S1-PadSD2)") (class "Default")
      (node (ref "NODEMCU-32S1") (pin "SD2") (pinfunction "SD2_SD2") (pintype "bidirectional"))
    )
    (net (code "67") (name "unconnected-(NODEMCU-32S1-PadSD3)") (class "Default")
      (node (ref "NODEMCU-32S1") (pin "SD3") (pinfunction "SD3_SD3") (pintype "bidirectional"))
    )
  )
)
